# 1_Supply.net
KiCad netlist of a schematic drawn in Altium Designer
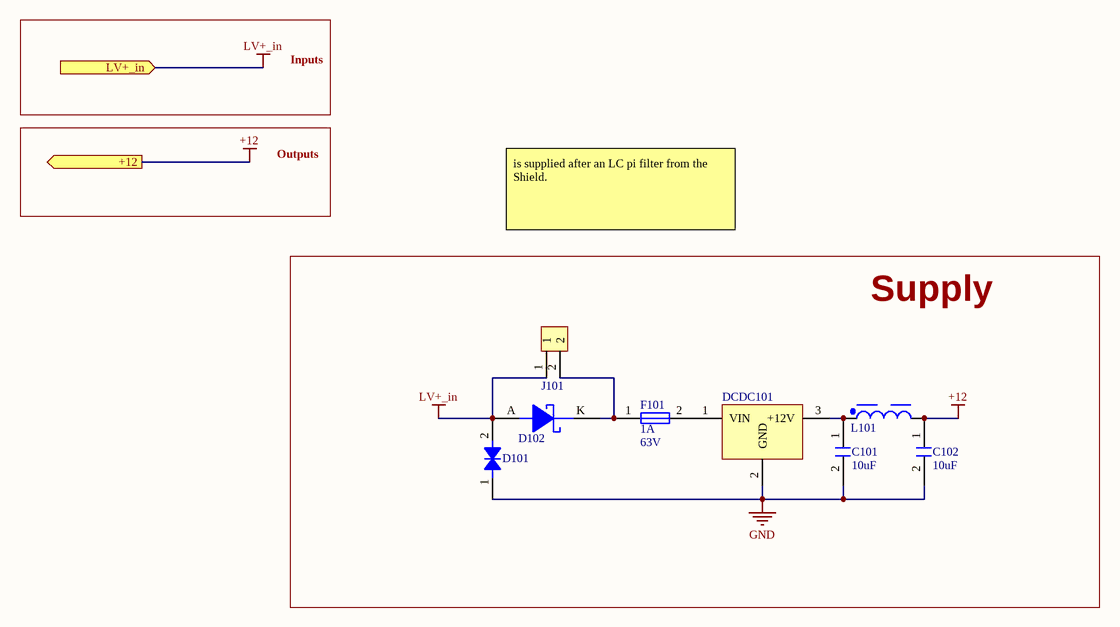
[diagram p0: [1] Supply.SchDoc]

(export (version "E")
  (design (tool "Eeschema 10.0.6"))
  (components
    (comp (ref "C101")
      (value "GRJ32ER71H106KE11L")
      (footprint "C10u-50V-1210FNPMLCC-X7R")
      (description "Multilayer Ceramic Capacitors MLCC - SMD/SMT 1210 10uF 50volts X7R +/-10% Soft Term")
      (fields
        (field (name "MANUFACTURER") "Murata")
        (field (name "TOLERANCE") "10%")
        (field (name "CAPACITANCE") "10uF")
        (field (name ".CREATOR") "DR")
      )
      (libsource (lib "Passives") (part "C10u-50V-1210FNPMLCC-X7R"))
    )
    (comp (ref "C102")
      (value "GRJ32ER71H106KE11L")
      (footprint "C10u-50V-1210FNPMLCC-X7R")
      (description "Multilayer Ceramic Capacitors MLCC - SMD/SMT 1210 10uF 50volts X7R +/-10% Soft Term")
      (fields
        (field (name "MANUFACTURER") "Murata")
        (field (name "TOLERANCE") "10%")
        (field (name "CAPACITANCE") "10uF")
        (field (name ".CREATOR") "DR")
      )
      (libsource (lib "Passives") (part "C10u-50V-1210FNPMLCC-X7R"))
    )
    (comp (ref "D101")
      (value "824551301")
      (footprint "DTVS-DO-214AB")
      (description "TVS diode [Würth Elektronik] 824551301 TVS diode")
      (fields (field (name "MANUFACTURER") "Wurth Electronics") (field (name ".CREATOR") "DO"))
      (libsource (lib "Filter components") (part "DTVS-40V-DO-214AB"))
    )
    (comp (ref "D102")
      (value "MBR0530")
      (footprint "DSC-SOD123")
      (description "VR=30V IF=500mA 30pF P=410mW")
      (fields (field (name ".CREATOR") "GP"))
      (libsource (lib "Filter components") (part "DSC-0.5/30-SOD123"))
    )
    (comp (ref "DCDC101")
      (value "173951236")
      (footprint "DCDC_Magi3c")
      (description "Fdsm Fixed Step Down Regulator M")
      (libsource (lib "Semiconductor") (part "DCDC-36V/12V-0.5A"))
    )
    (comp (ref "F101")
      (value "0437001.WRA")
      (footprint "Fuse_1206")
      (description "Fuse Chip Fast Acting 1A 63V SMD Solder Pad 1206 Ceramic T/R Automotive")
      (fields
        (field (name "MANUFACTURER") "Littelfuse")
        (field (name "CURRENT RATING") "1A")
        (field (name "VOLTAGE RATING (DC)") "63V")
        (field (name ".CREATOR") "DO")
      )
      (libsource (lib "Filter components") (part "Fuse_1A_63V_1206"))
    )
    (comp (ref "J101")
      (value "61300211121")
      (footprint "J_Pinheader_1x2")
      (description "CONN HEADER 2 POS 2.54")
      (fields (field (name "MANUFACTURER") "Molex") (field (name ".CREATOR") "GP"))
      (libsource (lib "Electromechanical") (part "J_Jumper"))
    )
    (comp (ref "L101")
      (value "744042470")
      (footprint "L_Power_ 47uH")
      (description "WE-TPC SMT Tiny Power Inductor, size 4818, 47uH, 0.62A, 540mOhm")
      (fields (field (name "MANUFACTURER") "Wurth Elektronik"))
      (libsource (lib "Passives") (part "L_47uH_0.6A"))
    )
  )
  (nets
    (net (code "1") (name "+12") (class "Default")
      (node (ref "C102") (pin "1") (pinfunction "1_1") (pintype "passive"))
      (node (ref "L101") (pin "2") (pinfunction "2_2") (pintype "passive"))
    )
    (net (code "2") (name "GND") (class "Default")
      (node (ref "C101") (pin "2") (pinfunction "2_2") (pintype "passive"))
      (node (ref "C102") (pin "2") (pinfunction "2_2") (pintype "passive"))
      (node (ref "D101") (pin "1") (pinfunction "1_1") (pintype "passive"))
      (node (ref "DCDC101") (pin "2") (pinfunction "GND_2") (pintype "passive"))
    )
    (net (code "3") (name "LV+_in") (class "Default")
      (node (ref "D101") (pin "2") (pinfunction "2_2") (pintype "passive"))
      (node (ref "D102") (pin "A") (pinfunction "A_A") (pintype "passive"))
      (node (ref "J101") (pin "1") (pinfunction "1_1") (pintype "passive"))
    )
    (net (code "4") (name "Net-(D102-PadK)") (class "Default")
      (node (ref "D102") (pin "K") (pinfunction "K_K") (pintype "passive"))
      (node (ref "F101") (pin "1") (pinfunction "1_1") (pintype "passive"))
      (node (ref "J101") (pin "2") (pinfunction "2_2") (pintype "passive"))
    )
    (net (code "5") (name "Net-(DCDC101-+12V)") (class "Default")
      (node (ref "C101") (pin "1") (pinfunction "1_1") (pintype "passive"))
      (node (ref "DCDC101") (pin "3") (pinfunction "+12V_3") (pintype "passive"))
      (node (ref "L101") (pin "1") (pinfunction "1_1") (pintype "passive"))
    )
    (net (code "6") (name "Net-(DCDC101-VIN)") (class "Default")
      (node (ref "DCDC101") (pin "1") (pinfunction "VIN_1") (pintype "passive"))
      (node (ref "F101") (pin "2") (pinfunction "2_2") (pintype "passive"))
    )
  )
)
